# bloxa.net
KiCad netlist of a schematic drawn in EAGLE
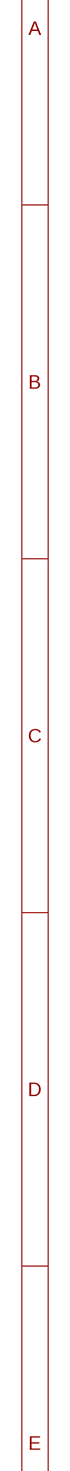
[diagram p0: schematic, sheet 1, part 1 of 2]
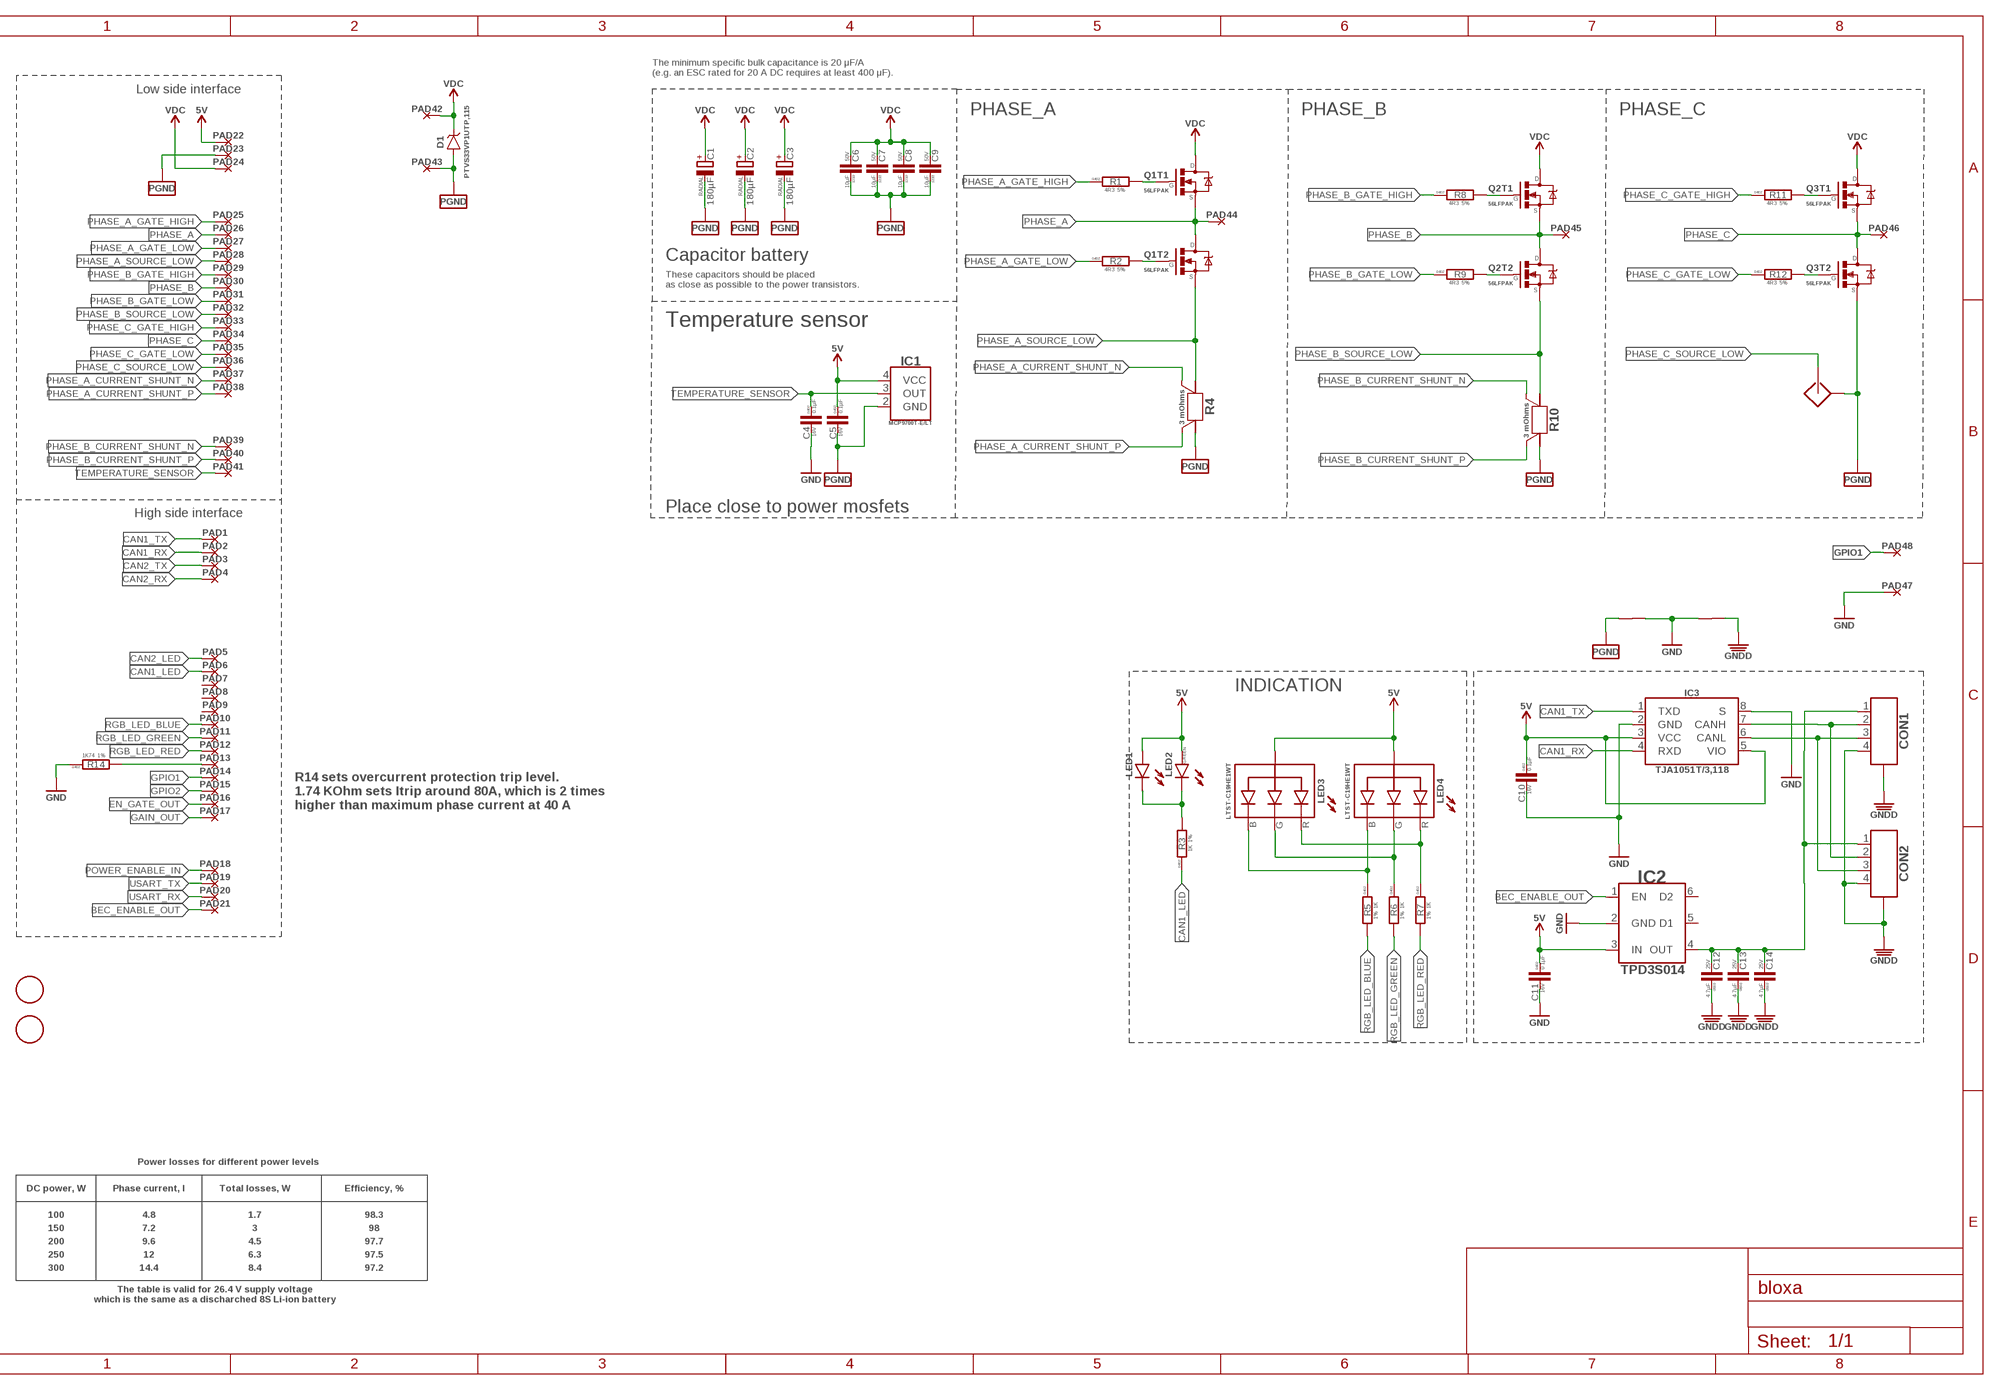
[diagram p1: schematic, sheet 1, part 2 of 2]

(export (version "E")
  (design (tool "Eeschema 10.0.6"))
  (components
    (comp (ref "C1")
      (value "180µF")
      (footprint "eagle-import:RADIAL_SIDE_8X21.5")
      (fields
        (field (name "PACKAGE") "RADIAL")
        (field (name "MANF") "United Chemi-Con")
        (field (name "VOLTAGE") "50V")
      )
      (libsource (lib "eagle-import") (part "CPOL-RADIAL_SIDE-8X21.5"))
    )
    (comp (ref "C2")
      (value "180µF")
      (footprint "eagle-import:RADIAL_SIDE_8X21.5")
      (fields
        (field (name "PACKAGE") "RADIAL")
        (field (name "MANF") "United Chemi-Con")
        (field (name "VOLTAGE") "50V")
      )
      (libsource (lib "eagle-import") (part "CPOL-RADIAL_SIDE-8X21.5"))
    )
    (comp (ref "C3")
      (value "180µF")
      (footprint "eagle-import:RADIAL_SIDE_8X21.5")
      (fields
        (field (name "PACKAGE") "RADIAL")
        (field (name "MANF") "United Chemi-Con")
        (field (name "VOLTAGE") "50V")
      )
      (libsource (lib "eagle-import") (part "CPOL-RADIAL_SIDE-8X21.5"))
    )
    (comp (ref "C4")
      (value "0.1µF")
      (footprint "eagle-import:C0402")
      (fields
        (field (name "MANF") "Murata Electronics North America")
        (field (name "PACKAGE") "0402")
        (field (name "TOLERANCE") "+-10%")
        (field (name "VOLTAGE") "16V")
      )
      (libsource (lib "eagle-import") (part "0.1µF-0402-16V_10%_X7R"))
    )
    (comp (ref "C5")
      (value "0.1µF")
      (footprint "eagle-import:C0402")
      (fields
        (field (name "MANF") "Murata Electronics North America")
        (field (name "PACKAGE") "0402")
        (field (name "TOLERANCE") "+-10%")
        (field (name "VOLTAGE") "16V")
      )
      (libsource (lib "eagle-import") (part "0.1µF-0402-16V_10%_X7R"))
    )
    (comp (ref "C6")
      (value "10µF")
      (footprint "eagle-import:C1210")
      (fields
        (field (name "MANF") "TDK Corporation")
        (field (name "PACKAGE") "1210")
        (field (name "TOLERANCE") "±10%")
        (field (name "VOLTAGE") "50V")
      )
      (libsource (lib "eagle-import") (part "10µF-C1210-50_10%_X7S"))
    )
    (comp (ref "C7")
      (value "10µF")
      (footprint "eagle-import:C1210")
      (fields
        (field (name "MANF") "TDK Corporation")
        (field (name "PACKAGE") "1210")
        (field (name "TOLERANCE") "±10%")
        (field (name "VOLTAGE") "50V")
      )
      (libsource (lib "eagle-import") (part "10µF-C1210-50_10%_X7S"))
    )
    (comp (ref "C8")
      (value "10µF")
      (footprint "eagle-import:C1210")
      (fields
        (field (name "MANF") "TDK Corporation")
        (field (name "PACKAGE") "1210")
        (field (name "TOLERANCE") "±10%")
        (field (name "VOLTAGE") "50V")
      )
      (libsource (lib "eagle-import") (part "10µF-C1210-50_10%_X7S"))
    )
    (comp (ref "C9")
      (value "10µF")
      (footprint "eagle-import:C1210")
      (fields
        (field (name "MANF") "TDK Corporation")
        (field (name "PACKAGE") "1210")
        (field (name "TOLERANCE") "±10%")
        (field (name "VOLTAGE") "50V")
      )
      (libsource (lib "eagle-import") (part "10µF-C1210-50_10%_X7S"))
    )
    (comp (ref "C10")
      (value "0.1µF")
      (footprint "eagle-import:C0402")
      (fields
        (field (name "MANF") "Murata Electronics North America")
        (field (name "PACKAGE") "0402")
        (field (name "TOLERANCE") "+-10%")
        (field (name "VOLTAGE") "16V")
      )
      (libsource (lib "eagle-import") (part "0.1µF-0402-16V_10%_X7R"))
    )
    (comp (ref "C11")
      (value "0.1µF")
      (footprint "eagle-import:C0402")
      (fields
        (field (name "MANF") "Murata Electronics North America")
        (field (name "PACKAGE") "0402")
        (field (name "TOLERANCE") "+-10%")
        (field (name "VOLTAGE") "16V")
      )
      (libsource (lib "eagle-import") (part "0.1µF-0402-16V_10%_X7R"))
    )
    (comp (ref "C12")
      (value "4.7µF")
      (footprint "eagle-import:C0603")
      (fields
        (field (name "MANF") "Murata Electronics North America")
        (field (name "PACKAGE") "0603")
        (field (name "TOLERANCE") "+-10%")
        (field (name "VOLTAGE") "25V")
      )
      (libsource (lib "eagle-import") (part "4.7µF-0603-25V_10%_X6S"))
    )
    (comp (ref "C13")
      (value "4.7µF")
      (footprint "eagle-import:C0603")
      (fields
        (field (name "MANF") "Murata Electronics North America")
        (field (name "PACKAGE") "0603")
        (field (name "TOLERANCE") "+-10%")
        (field (name "VOLTAGE") "25V")
      )
      (libsource (lib "eagle-import") (part "4.7µF-0603-25V_10%_X6S"))
    )
    (comp (ref "C14")
      (value "4.7µF")
      (footprint "eagle-import:C0603")
      (fields
        (field (name "MANF") "Murata Electronics North America")
        (field (name "PACKAGE") "0603")
        (field (name "TOLERANCE") "+-10%")
        (field (name "VOLTAGE") "25V")
      )
      (libsource (lib "eagle-import") (part "4.7µF-0603-25V_10%_X6S"))
    )
    (comp (ref "CON1")
      (value "CON-4P-JST_GH-RA")
      (footprint "eagle-import:JST_GH-4P-RA")
      (fields (field (name "MANF") "JST Sales America Inc"))
      (libsource (lib "eagle-import") (part "CON-4P-RA-JST_GH"))
    )
    (comp (ref "CON2")
      (value "CON-4P-JST_GH-RA")
      (footprint "eagle-import:JST_GH-4P-RA")
      (fields (field (name "MANF") "JST Sales America Inc"))
      (libsource (lib "eagle-import") (part "CON-4P-RA-JST_GH"))
    )
    (comp (ref "D1")
      (value "PTVS33VP1UTP,115-36V-SOD128")
      (footprint "eagle-import:SOD128")
      (fields (field (name "MANF") "Nexperia USA Inc") (field (name "MANF#") "PTVS33VP1UTP,115"))
      (libsource (lib "eagle-import") (part "PTVS33VP1UTP,115-SOD128-36V"))
    )
    (comp (ref "FD1")
      (value "FIDUCIALMOUNT")
      (footprint "eagle-import:FIDUCIA-MOUNT")
      (libsource (lib "eagle-import") (part "FIDUCIALMOUNT"))
    )
    (comp (ref "FD2")
      (value "FIDUCIALMOUNT")
      (footprint "eagle-import:FIDUCIA-MOUNT")
      (libsource (lib "eagle-import") (part "FIDUCIALMOUNT"))
    )
    (comp (ref "IC1")
      (value "MCP9700-SC70-5")
      (footprint "eagle-import:SC70-5")
      (fields (field (name "MANF#") "MCP9700T-E/LT") (field (name "MANF") "Microchip Technology"))
      (libsource (lib "eagle-import") (part "MCP9700-SC70-5"))
    )
    (comp (ref "IC2")
      (value "TPD3S014DBVR-SOT23-6")
      (footprint "eagle-import:SOT26")
      (fields (field (name "MANF") "Texas Instruments"))
      (libsource (lib "eagle-import") (part "TPD3S014DBVR-SOT23-6"))
    )
    (comp (ref "IC3")
      (value "TJA1051(X)/3-SO8")
      (footprint "eagle-import:SOIC8")
      (fields (field (name "MANF#") "TJA1051T/3,118") (field (name "MANF") "NXP USA Inc"))
      (libsource (lib "eagle-import") (part "TJA1051(X)/3-SO8"))
    )
    (comp (ref "J1")
      (value "CONNECTION")
      (footprint "eagle-import:CONNECTION")
      (libsource (lib "eagle-import") (part "CONNECTION"))
    )
    (comp (ref "J2")
      (value "CONNECTION")
      (footprint "eagle-import:CONNECTION")
      (libsource (lib "eagle-import") (part "CONNECTION"))
    )
    (comp (ref "LED1")
      (value "GREEN")
      (footprint "eagle-import:LED0402")
      (libsource (lib "eagle-import") (part "LED-0402"))
    )
    (comp (ref "LED2")
      (value "GREEN")
      (footprint "eagle-import:LED0402")
      (fields
        (field (name "COLOR") "GREEN")
        (field (name "DIGIKEY#") "1830-IN-S42BT5GCT-ND")
        (field (name "MANF") "Inolux")
        (field (name "MANF#") "IN-S42BT5G")
      )
      (libsource (lib "eagle-import") (part "LED-0402"))
    )
    (comp (ref "LED3")
      (value "LTST-C19HE1WT")
      (footprint "eagle-import:0606")
      (fields (field (name "MANF#") "LTST-C19HE1WT") (field (name "MANF") "Lite-On Inc"))
      (libsource (lib "eagle-import") (part "LTST-C19HE1WT"))
    )
    (comp (ref "LED4")
      (value "LTST-C19HE1WT")
      (footprint "eagle-import:0606")
      (fields (field (name "MANF#") "LTST-C19HE1WT") (field (name "MANF") "Lite-On Inc"))
      (libsource (lib "eagle-import") (part "LTST-C19HE1WT"))
    )
    (comp (ref "PAD1")
      (value "PAD-1X1.5")
      (footprint "eagle-import:SMD_1X1,5")
      (libsource (lib "eagle-import") (part "PAD-1X1.5"))
    )
    (comp (ref "PAD2")
      (value "PAD-1X1.5")
      (footprint "eagle-import:SMD_1X1,5")
      (libsource (lib "eagle-import") (part "PAD-1X1.5"))
    )
    (comp (ref "PAD3")
      (value "PAD-1X1.5")
      (footprint "eagle-import:SMD_1X1,5")
      (libsource (lib "eagle-import") (part "PAD-1X1.5"))
    )
    (comp (ref "PAD4")
      (value "PAD-1X1.5")
      (footprint "eagle-import:SMD_1X1,5")
      (libsource (lib "eagle-import") (part "PAD-1X1.5"))
    )
    (comp (ref "PAD5")
      (value "PAD-HOLE-0.6")
      (footprint "eagle-import:HOLE_0.6")
      (libsource (lib "eagle-import") (part "PAD-HOLE-0.6"))
    )
    (comp (ref "PAD6")
      (value "PAD-HOLE-0.6")
      (footprint "eagle-import:HOLE_0.6")
      (libsource (lib "eagle-import") (part "PAD-HOLE-0.6"))
    )
    (comp (ref "PAD7")
      (value "PAD-HOLE-0.6")
      (footprint "eagle-import:HOLE_0.6")
      (libsource (lib "eagle-import") (part "PAD-HOLE-0.6"))
    )
    (comp (ref "PAD8")
      (value "PAD-HOLE-0.6")
      (footprint "eagle-import:HOLE_0.6")
      (libsource (lib "eagle-import") (part "PAD-HOLE-0.6"))
    )
    (comp (ref "PAD9")
      (value "PAD-HOLE-0.6")
      (footprint "eagle-import:HOLE_0.6")
      (libsource (lib "eagle-import") (part "PAD-HOLE-0.6"))
    )
    (comp (ref "PAD10")
      (value "PAD-HOLE-0.6")
      (footprint "eagle-import:HOLE_0.6")
      (libsource (lib "eagle-import") (part "PAD-HOLE-0.6"))
    )
    (comp (ref "PAD11")
      (value "PAD-HOLE-0.6")
      (footprint "eagle-import:HOLE_0.6")
      (libsource (lib "eagle-import") (part "PAD-HOLE-0.6"))
    )
    (comp (ref "PAD12")
      (value "PAD-HOLE-0.6")
      (footprint "eagle-import:HOLE_0.6")
      (libsource (lib "eagle-import") (part "PAD-HOLE-0.6"))
    )
    (comp (ref "PAD13")
      (value "PAD-HOLE-0.6")
      (footprint "eagle-import:HOLE_0.6")
      (libsource (lib "eagle-import") (part "PAD-HOLE-0.6"))
    )
    (comp (ref "PAD14")
      (value "PAD-HOLE-0.6")
      (footprint "eagle-import:HOLE_0.6")
      (libsource (lib "eagle-import") (part "PAD-HOLE-0.6"))
    )
    (comp (ref "PAD15")
      (value "PAD-HOLE-0.6")
      (footprint "eagle-import:HOLE_0.6")
      (libsource (lib "eagle-import") (part "PAD-HOLE-0.6"))
    )
    (comp (ref "PAD16")
      (value "PAD-HOLE-0.6")
      (footprint "eagle-import:HOLE_0.6")
      (libsource (lib "eagle-import") (part "PAD-HOLE-0.6"))
    )
    (comp (ref "PAD17")
      (value "PAD-HOLE-0.6")
      (footprint "eagle-import:HOLE_0.6")
      (libsource (lib "eagle-import") (part "PAD-HOLE-0.6"))
    )
    (comp (ref "PAD18")
      (value "PAD-HOLE-0.6")
      (footprint "eagle-import:HOLE_0.6")
      (libsource (lib "eagle-import") (part "PAD-HOLE-0.6"))
    )
    (comp (ref "PAD19")
      (value "PAD-HOLE-0.6")
      (footprint "eagle-import:HOLE_0.6")
      (libsource (lib "eagle-import") (part "PAD-HOLE-0.6"))
    )
    (comp (ref "PAD20")
      (value "PAD-HOLE-0.6")
      (footprint "eagle-import:HOLE_0.6")
      (libsource (lib "eagle-import") (part "PAD-HOLE-0.6"))
    )
    (comp (ref "PAD21")
      (value "PAD-HOLE-0.6")
      (footprint "eagle-import:HOLE_0.6")
      (libsource (lib "eagle-import") (part "PAD-HOLE-0.6"))
    )
    (comp (ref "PAD22")
      (value "PAD-1X1.5")
      (footprint "eagle-import:SMD_1X1,5")
      (libsource (lib "eagle-import") (part "PAD-1X1.5"))
    )
    (comp (ref "PAD23")
      (value "PAD-1X1.5")
      (footprint "eagle-import:SMD_1X1,5")
      (libsource (lib "eagle-import") (part "PAD-1X1.5"))
    )
    (comp (ref "PAD24")
      (value "PAD-1X1.5")
      (footprint "eagle-import:SMD_1X1,5")
      (libsource (lib "eagle-import") (part "PAD-1X1.5"))
    )
    (comp (ref "PAD25")
      (value "PAD-HOLE-0.6")
      (footprint "eagle-import:HOLE_0.6")
      (libsource (lib "eagle-import") (part "PAD-HOLE-0.6"))
    )
    (comp (ref "PAD26")
      (value "PAD-HOLE-0.6")
      (footprint "eagle-import:HOLE_0.6")
      (libsource (lib "eagle-import") (part "PAD-HOLE-0.6"))
    )
    (comp (ref "PAD27")
      (value "PAD-HOLE-0.6")
      (footprint "eagle-import:HOLE_0.6")
      (libsource (lib "eagle-import") (part "PAD-HOLE-0.6"))
    )
    (comp (ref "PAD28")
      (value "PAD-HOLE-0.6")
      (footprint "eagle-import:HOLE_0.6")
      (libsource (lib "eagle-import") (part "PAD-HOLE-0.6"))
    )
    (comp (ref "PAD29")
      (value "PAD-HOLE-0.6")
      (footprint "eagle-import:HOLE_0.6")
      (libsource (lib "eagle-import") (part "PAD-HOLE-0.6"))
    )
    (comp (ref "PAD30")
      (value "PAD-HOLE-0.6")
      (footprint "eagle-import:HOLE_0.6")
      (libsource (lib "eagle-import") (part "PAD-HOLE-0.6"))
    )
    (comp (ref "PAD31")
      (value "PAD-HOLE-0.6")
      (footprint "eagle-import:HOLE_0.6")
      (libsource (lib "eagle-import") (part "PAD-HOLE-0.6"))
    )
    (comp (ref "PAD32")
      (value "PAD-HOLE-0.6")
      (footprint "eagle-import:HOLE_0.6")
      (libsource (lib "eagle-import") (part "PAD-HOLE-0.6"))
    )
    (comp (ref "PAD33")
      (value "PAD-HOLE-0.6")
      (footprint "eagle-import:HOLE_0.6")
      (libsource (lib "eagle-import") (part "PAD-HOLE-0.6"))
    )
    (comp (ref "PAD34")
      (value "PAD-HOLE-0.6")
      (footprint "eagle-import:HOLE_0.6")
      (libsource (lib "eagle-import") (part "PAD-HOLE-0.6"))
    )
    (comp (ref "PAD35")
      (value "PAD-HOLE-0.6")
      (footprint "eagle-import:HOLE_0.6")
      (libsource (lib "eagle-import") (part "PAD-HOLE-0.6"))
    )
    (comp (ref "PAD36")
      (value "PAD-HOLE-0.6")
      (footprint "eagle-import:HOLE_0.6")
      (libsource (lib "eagle-import") (part "PAD-HOLE-0.6"))
    )
    (comp (ref "PAD37")
      (value "PAD-HOLE-0.6")
      (footprint "eagle-import:HOLE_0.6")
      (libsource (lib "eagle-import") (part "PAD-HOLE-0.6"))
    )
    (comp (ref "PAD38")
      (value "PAD-HOLE-0.6")
      (footprint "eagle-import:HOLE_0.6")
      (libsource (lib "eagle-import") (part "PAD-HOLE-0.6"))
    )
    (comp (ref "PAD39")
      (value "PAD-HOLE-0.6")
      (footprint "eagle-import:HOLE_0.6")
      (libsource (lib "eagle-import") (part "PAD-HOLE-0.6"))
    )
    (comp (ref "PAD40")
      (value "PAD-HOLE-0.6")
      (footprint "eagle-import:HOLE_0.6")
      (libsource (lib "eagle-import") (part "PAD-HOLE-0.6"))
    )
    (comp (ref "PAD41")
      (value "PAD-HOLE-0.6")
      (footprint "eagle-import:HOLE_0.6")
      (libsource (lib "eagle-import") (part "PAD-HOLE-0.6"))
    )
    (comp (ref "PAD42")
      (value "PAD-4X2")
      (footprint "eagle-import:4X2")
      (libsource (lib "eagle-import") (part "PAD-4X2"))
    )
    (comp (ref "PAD43")
      (value "PAD-4X2")
      (footprint "eagle-import:4X2")
      (libsource (lib "eagle-import") (part "PAD-4X2"))
    )
    (comp (ref "PAD44")
      (value "PAD-HOLE_1.5")
      (footprint "eagle-import:HOLE_1.5")
      (libsource (lib "eagle-import") (part "PAD-HOLE_1.5"))
    )
    (comp (ref "PAD45")
      (value "PAD-HOLE_1.5")
      (footprint "eagle-import:HOLE_1.5")
      (libsource (lib "eagle-import") (part "PAD-HOLE_1.5"))
    )
    (comp (ref "PAD46")
      (value "PAD-HOLE_1.5")
      (footprint "eagle-import:HOLE_1.5")
      (libsource (lib "eagle-import") (part "PAD-HOLE_1.5"))
    )
    (comp (ref "PAD47")
      (value "PAD-S-1.5")
      (footprint "eagle-import:1.5X1.5")
      (libsource (lib "eagle-import") (part "PAD-S-1.5"))
    )
    (comp (ref "PAD48")
      (value "PAD-S-1.5")
      (footprint "eagle-import:1.5X1.5")
      (libsource (lib "eagle-import") (part "PAD-S-1.5"))
    )
    (comp (ref "Q1")
      (value "BUK9K6R2-40E,115")
      (footprint "eagle-import:SOT-1205")
      (fields (field (name "PACKAGE") "56LFPAK") (field (name "MANF") "NXP Semiconductors"))
      (libsource (lib "eagle-import") (part "BUK9K6R2-40E,115"))
    )
    (comp (ref "Q2")
      (value "BUK9K6R2-40E,115")
      (footprint "eagle-import:SOT-1205")
      (fields (field (name "PACKAGE") "56LFPAK") (field (name "MANF") "NXP Semiconductors"))
      (libsource (lib "eagle-import") (part "BUK9K6R2-40E,115"))
    )
    (comp (ref "Q3")
      (value "BUK9K6R2-40E,115")
      (footprint "eagle-import:SOT-1205")
      (fields (field (name "PACKAGE") "56LFPAK") (field (name "MANF") "NXP Semiconductors"))
      (libsource (lib "eagle-import") (part "BUK9K6R2-40E,115"))
    )
    (comp (ref "R1")
      (value "4R3")
      (footprint "eagle-import:R0402")
      (fields (field (name "MANF") "Yageo") (field (name "PACKAGE") "0402") (field (name "TOLERANCE") "5%"))
      (libsource (lib "eagle-import") (part "4R3-0402-5%"))
    )
    (comp (ref "R2")
      (value "4R3")
      (footprint "eagle-import:R0402")
      (fields (field (name "MANF") "Yageo") (field (name "PACKAGE") "0402") (field (name "TOLERANCE") "5%"))
      (libsource (lib "eagle-import") (part "4R3-0402-5%"))
    )
    (comp (ref "R3")
      (value "1K")
      (footprint "eagle-import:R0402")
      (fields (field (name "MANF") "Yageo") (field (name "PACKAGE") "0402") (field (name "TOLERANCE") "1%"))
      (libsource (lib "eagle-import") (part "1K-0402-1%"))
    )
    (comp (ref "R4")
      (value "3 mOhms")
      (footprint "eagle-import:R2512-KELVIN")
      (fields
        (field (name "MANF") "Stackpole Electronics Inc")
        (field (name "POWER") "2W")
        (field (name "TOLERANCE") "±1%")
        (field (name "DIGIKEY#") "2019-TLR3APSDTE3L00F50CT-ND")
        (field (name "MANF_1") "KOA Speer Electronics, Inc.")
        (field (name "MANF#") "TLR3APSDTE3L00F50")
        (field (name "POWER_1") "5W")
      )
      (libsource (lib "eagle-import") (part "CURRENT_SHUNT_KELVIN-2512-KELVIN-0.010R"))
    )
    (comp (ref "R5")
      (value "1K")
      (footprint "eagle-import:R0402")
      (fields (field (name "MANF") "Yageo") (field (name "PACKAGE") "0402") (field (name "TOLERANCE") "1%"))
      (libsource (lib "eagle-import") (part "1K-0402-1%"))
    )
    (comp (ref "R6")
      (value "1K")
      (footprint "eagle-import:R0402")
      (fields (field (name "MANF") "Yageo") (field (name "PACKAGE") "0402") (field (name "TOLERANCE") "1%"))
      (libsource (lib "eagle-import") (part "1K-0402-1%"))
    )
    (comp (ref "R7")
      (value "1K")
      (footprint "eagle-import:R0402")
      (fields (field (name "MANF") "Yageo") (field (name "PACKAGE") "0402") (field (name "TOLERANCE") "1%"))
      (libsource (lib "eagle-import") (part "1K-0402-1%"))
    )
    (comp (ref "R8")
      (value "4R3")
      (footprint "eagle-import:R0402")
      (fields (field (name "MANF") "Yageo") (field (name "PACKAGE") "0402") (field (name "TOLERANCE") "5%"))
      (libsource (lib "eagle-import") (part "4R3-0402-5%"))
    )
    (comp (ref "R9")
      (value "4R3")
      (footprint "eagle-import:R0402")
      (fields (field (name "MANF") "Yageo") (field (name "PACKAGE") "0402") (field (name "TOLERANCE") "5%"))
      (libsource (lib "eagle-import") (part "4R3-0402-5%"))
    )
    (comp (ref "R10")
      (value "3 mOhms")
      (footprint "eagle-import:R2512-KELVIN")
      (fields
        (field (name "MANF") "Stackpole Electronics Inc")
        (field (name "POWER") "2W")
        (field (name "TOLERANCE") "±1%")
        (field (name "DIGIKEY#") "2019-TLR3APSDTE3L00F50CT-ND")
        (field (name "MANF_1") "KOA Speer Electronics, Inc.")
        (field (name "MANF#") "TLR3APSDTE3L00F50")
        (field (name "POWER_1") "5W")
      )
      (libsource (lib "eagle-import") (part "CURRENT_SHUNT_KELVIN-2512-KELVIN-0.010R"))
    )
    (comp (ref "R11")
      (value "4R3")
      (footprint "eagle-import:R0402")
      (fields (field (name "MANF") "Yageo") (field (name "PACKAGE") "0402") (field (name "TOLERANCE") "5%"))
      (libsource (lib "eagle-import") (part "4R3-0402-5%"))
    )
    (comp (ref "R12")
      (value "4R3")
      (footprint "eagle-import:R0402")
      (fields (field (name "MANF") "Yageo") (field (name "PACKAGE") "0402") (field (name "TOLERANCE") "5%"))
      (libsource (lib "eagle-import") (part "4R3-0402-5%"))
    )
    (comp (ref "R14")
      (value "1K74")
      (footprint "eagle-import:R0402")
      (fields
        (field (name "PACKAGE") "0402")
        (field (name "TOLERANCE") "1%")
        (field (name "AEC-Q") "AEC-Q200")
        (field (name "DIGIKEY#") "541-1.74KLCT-ND")
        (field (name "MANF") "Vishay Dale")
        (field (name "MANF#") "CRCW04021K74FKED")
      )
      (libsource (lib "eagle-import") (part "R-0402-1%"))
    )
    (comp (ref "S1")
      (value "SENSE")
      (footprint "eagle-import:SENSE-0.6")
      (libsource (lib "eagle-import") (part "SENSE"))
    )
  )
  (nets
    (net (code "1") (name "5V") (class "Default")
      (node (ref "C10") (pin "1") (pinfunction "1_1") (pintype "passive"))
      (node (ref "C11") (pin "1") (pinfunction "1_1") (pintype "passive"))
      (node (ref "C5") (pin "1") (pinfunction "1_1") (pintype "passive"))
      (node (ref "IC1") (pin "4") (pinfunction "VCC_4") (pintype "bidirectional"))
      (node (ref "IC2") (pin "3") (pinfunction "IN_3") (pintype "bidirectional"))
      (node (ref "IC3") (pin "3") (pinfunction "VCC_3") (pintype "bidirectional"))
      (node (ref "IC3") (pin "5") (pinfunction "VIO_5") (pintype "bidirectional"))
      (node (ref "LED1") (pin "A") (pinfunction "A_A") (pintype "bidirectional"))
      (node (ref "LED2") (pin "A") (pinfunction "A_A") (pintype "bidirectional"))
      (node (ref "LED3") (pin "+") (pinfunction "A_+") (pintype "bidirectional"))
      (node (ref "LED4") (pin "+") (pinfunction "A_+") (pintype "bidirectional"))
      (node (ref "PAD22") (pin "P$1") (pinfunction "P$1_P$1") (pintype "bidirectional"))
    )
    (net (code "2") (name "BEC_ENABLE_OUT") (class "Default")
      (node (ref "IC2") (pin "1") (pinfunction "EN_1") (pintype "bidirectional"))
      (node (ref "PAD21") (pin "P$1") (pinfunction "P$1_P$1") (pintype "bidirectional"))
    )
    (net (code "3") (name "CAN1_LED") (class "Default")
      (node (ref "PAD6") (pin "P$1") (pinfunction "P$1_P$1") (pintype "bidirectional"))
      (node (ref "R3") (pin "1") (pinfunction "1_1") (pintype "passive"))
    )
    (net (code "4") (name "CAN1_RX") (class "Default")
      (node (ref "IC3") (pin "4") (pinfunction "RXD_4") (pintype "bidirectional"))
      (node (ref "PAD2") (pin "P$1") (pinfunction "P$1_P$1") (pintype "bidirectional"))
    )
    (net (code "5") (name "CAN1_TX") (class "Default")
      (node (ref "IC3") (pin "1") (pinfunction "TXD_1") (pintype "bidirectional"))
      (node (ref "PAD1") (pin "P$1") (pinfunction "P$1_P$1") (pintype "bidirectional"))
    )
    (net (code "6") (name "CAN2_LED") (class "Default")
      (node (ref "PAD5") (pin "P$1") (pinfunction "P$1_P$1") (pintype "bidirectional"))
    )
    (net (code "7") (name "CAN2_RX") (class "Default")
      (node (ref "PAD4") (pin "P$1") (pinfunction "P$1_P$1") (pintype "bidirectional"))
    )
    (net (code "8") (name "CAN2_TX") (class "Default")
      (node (ref "PAD3") (pin "P$1") (pinfunction "P$1_P$1") (pintype "bidirectional"))
    )
    (net (code "9") (name "EN_GATE_OUT") (class "Default")
      (node (ref "PAD16") (pin "P$1") (pinfunction "P$1_P$1") (pintype "bidirectional"))
    )
    (net (code "10") (name "GAIN_OUT") (class "Default")
      (node (ref "PAD17") (pin "P$1") (pinfunction "P$1_P$1") (pintype "bidirectional"))
    )
    (net (code "11") (name "GND") (class "Default")
      (node (ref "C10") (pin "2") (pinfunction "2_2") (pintype "passive"))
      (node (ref "C11") (pin "2") (pinfunction "2_2") (pintype "passive"))
      (node (ref "C4") (pin "2") (pinfunction "2_2") (pintype "passive"))
      (node (ref "IC2") (pin "2") (pinfunction "GND_2") (pintype "bidirectional"))
      (node (ref "IC3") (pin "2") (pinfunction "GND_2") (pintype "bidirectional"))
      (node (ref "IC3") (pin "8") (pinfunction "S_8") (pintype "bidirectional"))
      (node (ref "J1") (pin "P$1") (pinfunction "P$1_P$1") (pintype "bidirectional"))
      (node (ref "J2") (pin "P$1") (pinfunction "P$1_P$1") (pintype "bidirectional"))
      (node (ref "PAD47") (pin "P$1") (pinfunction "P$1_P$1") (pintype "bidirectional"))
      (node (ref "R14") (pin "1") (pinfunction "1_1") (pintype "passive"))
    )
    (net (code "12") (name "GNDD") (class "Default")
      (node (ref "C12") (pin "P$1") (pinfunction "1_P$1") (pintype "passive"))
      (node (ref "C13") (pin "P$1") (pinfunction "1_P$1") (pintype "passive"))
      (node (ref "C14") (pin "P$1") (pinfunction "1_P$1") (pintype "passive"))
      (node (ref "CON1") (pin "4") (pinfunction "4_4") (pintype "bidirectional"))
      (node (ref "CON1") (pin "M$0") (pinfunction "GND_M$0") (pintype "bidirectional"))
      (node (ref "CON1") (pin "M$1") (pinfunction "GND_M$1") (pintype "bidirectional"))
      (node (ref "CON2") (pin "4") (pinfunction "4_4") (pintype "bidirectional"))
      (node (ref "CON2") (pin "M$0") (pinfunction "GND_M$0") (pintype "bidirectional"))
      (node (ref "CON2") (pin "M$1") (pinfunction "GND_M$1") (pintype "bidirectional"))
      (node (ref "J2") (pin "P$2") (pinfunction "P$2_P$2") (pintype "bidirectional"))
    )
    (net (code "13") (name "GPIO1") (class "Default")
      (node (ref "PAD14") (pin "P$1") (pinfunction "P$1_P$1") (pintype "bidirectional"))
      (node (ref "PAD48") (pin "P$1") (pinfunction "P$1_P$1") (pintype "bidirectional"))
    )
    (net (code "14") (name "GPIO2") (class "Default")
      (node (ref "PAD15") (pin "P$1") (pinfunction "P$1_P$1") (pintype "bidirectional"))
    )
    (net (code "15") (name "Net-(C12-2)") (class "Default")
      (node (ref "C12") (pin "P$2") (pinfunction "2_P$2") (pintype "passive"))
      (node (ref "C13") (pin "P$2") (pinfunction "2_P$2") (pintype "passive"))
      (node (ref "C14") (pin "P$2") (pinfunction "2_P$2") (pintype "passive"))
      (node (ref "CON1") (pin "1") (pinfunction "1_1") (pintype "bidirectional"))
      (node (ref "CON2") (pin "1") (pinfunction "1_1") (pintype "bidirectional"))
      (node (ref "IC2") (pin "4") (pinfunction "OUT_4") (pintype "bidirectional"))
    )
    (net (code "16") (name "Net-(IC3-CANH)") (class "Default")
      (node (ref "CON1") (pin "2") (pinfunction "2_2") (pintype "bidirectional"))
      (node (ref "CON2") (pin "2") (pinfunction "2_2") (pintype "bidirectional"))
      (node (ref "IC3") (pin "7") (pinfunction "CANH_7") (pintype "bidirectional"))
    )
    (net (code "17") (name "Net-(IC3-CANL)") (class "Default")
      (node (ref "CON1") (pin "3") (pinfunction "3_3") (pintype "bidirectional"))
      (node (ref "CON2") (pin "3") (pinfunction "3_3") (pintype "bidirectional"))
      (node (ref "IC3") (pin "6") (pinfunction "CANL_6") (pintype "bidirectional"))
    )
    (net (code "18") (name "Net-(LED1-PadC)") (class "Default")
      (node (ref "LED1") (pin "C") (pinfunction "C_C") (pintype "bidirectional"))
      (node (ref "LED2") (pin "C") (pinfunction "C_C") (pintype "bidirectional"))
      (node (ref "R3") (pin "2") (pinfunction "2_2") (pintype "passive"))
    )
    (net (code "19") (name "Net-(LED3-PadB)") (class "Default")
      (node (ref "LED3") (pin "B") (pinfunction "B_B") (pintype "bidirectional"))
      (node (ref "LED4") (pin "B") (pinfunction "B_B") (pintype "bidirectional"))
      (node (ref "R5") (pin "1") (pinfunction "1_1") (pintype "passive"))
    )
    (net (code "20") (name "Net-(LED3-PadG)") (class "Default")
      (node (ref "LED3") (pin "G") (pinfunction "G_G") (pintype "bidirectional"))
      (node (ref "LED4") (pin "G") (pinfunction "G_G") (pintype "bidirectional"))
      (node (ref "R6") (pin "1") (pinfunction "1_1") (pintype "passive"))
    )
    (net (code "21") (name "Net-(LED3-PadR)") (class "Default")
      (node (ref "LED3") (pin "R") (pinfunction "R_R") (pintype "bidirectional"))
      (node (ref "LED4") (pin "R") (pinfunction "R_R") (pintype "bidirectional"))
      (node (ref "R7") (pin "1") (pinfunction "1_1") (pintype "passive"))
    )
    (net (code "22") (name "Net-(PAD13-PadP$1)") (class "Default")
      (node (ref "PAD13") (pin "P$1") (pinfunction "P$1_P$1") (pintype "bidirectional"))
      (node (ref "R14") (pin "2") (pinfunction "2_2") (pintype "passive"))
    )
    (net (code "23") (name "Net-(Q1A-G)") (class "Default")
      (node (ref "Q1") (pin "2") (pinfunction "G_2") (pintype "passive"))
      (node (ref "R1") (pin "2") (pinfunction "2_2") (pintype "passive"))
    )
    (net (code "24") (name "Net-(Q1B-G)") (class "Default")
      (node (ref "Q1") (pin "4") (pinfunction "G_4") (pintype "passive"))
      (node (ref "R2") (pin "2") (pinfunction "2_2") (pintype "passive"))
    )
    (net (code "25") (name "Net-(Q2A-G)") (class "Default")
      (node (ref "Q2") (pin "2") (pinfunction "G_2") (pintype "passive"))
      (node (ref "R8") (pin "2") (pinfunction "2_2") (pintype "passive"))
    )
    (net (code "26") (name "Net-(Q2B-G)") (class "Default")
      (node (ref "Q2") (pin "4") (pinfunction "G_4") (pintype "passive"))
      (node (ref "R9") (pin "2") (pinfunction "2_2") (pintype "passive"))
    )
    (net (code "27") (name "Net-(Q3A-G)") (class "Default")
      (node (ref "Q3") (pin "2") (pinfunction "G_2") (pintype "passive"))
      (node (ref "R11") (pin "2") (pinfunction "2_2") (pintype "passive"))
    )
    (net (code "28") (name "Net-(Q3B-G)") (class "Default")
      (node (ref "Q3") (pin "4") (pinfunction "G_4") (pintype "passive"))
      (node (ref "R12") (pin "2") (pinfunction "2_2") (pintype "passive"))
    )
    (net (code "29") (name "PGND") (class "Default")
      (node (ref "C1") (pin "-") (pinfunction "-_-") (pintype "passive"))
      (node (ref "C2") (pin "-") (pinfunction "-_-") (pintype "passive"))
      (node (ref "C3") (pin "-") (pinfunction "-_-") (pintype "passive"))
      (node (ref "C5") (pin "2") (pinfunction "2_2") (pintype "passive"))
      (node (ref "C6") (pin "1") (pinfunction "1_1") (pintype "passive"))
      (node (ref "C7") (pin "1") (pinfunction "1_1") (pintype "passive"))
      (node (ref "C8") (pin "1") (pinfunction "1_1") (pintype "passive"))
      (node (ref "C9") (pin "1") (pinfunction "1_1") (pintype "passive"))
      (node (ref "D1") (pin "A") (pinfunction "A_A") (pintype "passive"))
      (node (ref "IC1") (pin "2") (pinfunction "GND_2") (pintype "bidirectional"))
      (node (ref "J1") (pin "P$2") (pinfunction "P$2_P$2") (pintype "bidirectional"))
      (node (ref "PAD23") (pin "P$1") (pinfunction "P$1_P$1") (pintype "bidirectional"))
      (node (ref "PAD43") (pin "P$1") (pinfunction "P$1_P$1") (pintype "bidirectional"))
      (node (ref "Q3") (pin "3") (pinfunction "S_3") (pintype "passive"))
      (node (ref "R10") (pin "2") (pinfunction "2_2") (pintype "bidirectional"))
      (node (ref "R10") (pin "22") (pinfunction "2_22") (pintype "bidirectional"))
      (node (ref "R4") (pin "2") (pinfunction "2_2") (pintype "bidirectional"))
      (node (ref "R4") (pin "22") (pinfunction "2_22") (pintype "bidirectional"))
      (node (ref "S1") (pin "SHELL") (pinfunction "SHELLL_SHELL") (pintype "bidirectional"))
    )
    (net (code "30") (name "PHASE_A") (class "Default")
      (node (ref "PAD26") (pin "P$1") (pinfunction "P$1_P$1") (pintype "bidirectional"))
      (node (ref "PAD44") (pin "P$1") (pinfunction "P$1_P$1") (pintype "bidirectional"))
      (node (ref "Q1") (pin "1") (pinfunction "S_1") (pintype "passive"))
      (node (ref "Q1") (pin "5") (pinfunction "D_5") (pintype "passive"))
      (node (ref "Q1") (pin "6") (pinfunction "D_6") (pintype "passive"))
      (node (ref "Q1") (pin "EP-5-6") (pinfunction "D_EP-5-6") (pintype "passive"))
    )
    (net (code "31") (name "PHASE_A_CURRENT_SHUNT_N") (class "Default")
      (node (ref "PAD37") (pin "P$1") (pinfunction "P$1_P$1") (pintype "bidirectional"))
      (node (ref "R4") (pin "S1") (pinfunction "S1_S1") (pintype "bidirectional"))
    )
    (net (code "32") (name "PHASE_A_CURRENT_SHUNT_P") (class "Default")
      (node (ref "PAD38") (pin "P$1") (pinfunction "P$1_P$1") (pintype "bidirectional"))
      (node (ref "R4") (pin "S2") (pinfunction "S2_S2") (pintype "bidirectional"))
    )
    (net (code "33") (name "PHASE_A_GATE_HIGH") (class "Default")
      (node (ref "PAD25") (pin "P$1") (pinfunction "P$1_P$1") (pintype "bidirectional"))
      (node (ref "R1") (pin "1") (pinfunction "1_1") (pintype "passive"))
    )
    (net (code "34") (name "PHASE_A_GATE_LOW") (class "Default")
      (node (ref "PAD27") (pin "P$1") (pinfunction "P$1_P$1") (pintype "bidirectional"))
      (node (ref "R2") (pin "1") (pinfunction "1_1") (pintype "passive"))
    )
    (net (code "35") (name "PHASE_A_SOURCE_LOW") (class "Default")
      (node (ref "PAD28") (pin "P$1") (pinfunction "P$1_P$1") (pintype "bidirectional"))
      (node (ref "Q1") (pin "3") (pinfunction "S_3") (pintype "passive"))
      (node (ref "R4") (pin "1") (pinfunction "1_1") (pintype "bidirectional"))
      (node (ref "R4") (pin "11") (pinfunction "1_11") (pintype "bidirectional"))
    )
    (net (code "36") (name "PHASE_B") (class "Default")
      (node (ref "PAD30") (pin "P$1") (pinfunction "P$1_P$1") (pintype "bidirectional"))
      (node (ref "PAD45") (pin "P$1") (pinfunction "P$1_P$1") (pintype "bidirectional"))
      (node (ref "Q2") (pin "1") (pinfunction "S_1") (pintype "passive"))
      (node (ref "Q2") (pin "5") (pinfunction "D_5") (pintype "passive"))
      (node (ref "Q2") (pin "6") (pinfunction "D_6") (pintype "passive"))
      (node (ref "Q2") (pin "EP-5-6") (pinfunction "D_EP-5-6") (pintype "passive"))
    )
    (net (code "37") (name "PHASE_B_CURRENT_SHUNT_N") (class "Default")
      (node (ref "PAD39") (pin "P$1") (pinfunction "P$1_P$1") (pintype "bidirectional"))
      (node (ref "R10") (pin "S1") (pinfunction "S1_S1") (pintype "bidirectional"))
    )
    (net (code "38") (name "PHASE_B_CURRENT_SHUNT_P") (class "Default")
      (node (ref "PAD40") (pin "P$1") (pinfunction "P$1_P$1") (pintype "bidirectional"))
      (node (ref "R10") (pin "S2") (pinfunction "S2_S2") (pintype "bidirectional"))
    )
    (net (code "39") (name "PHASE_B_GATE_HIGH") (class "Default")
      (node (ref "PAD29") (pin "P$1") (pinfunction "P$1_P$1") (pintype "bidirectional"))
      (node (ref "R8") (pin "1") (pinfunction "1_1") (pintype "passive"))
    )
    (net (code "40") (name "PHASE_B_GATE_LOW") (class "Default")
      (node (ref "PAD31") (pin "P$1") (pinfunction "P$1_P$1") (pintype "bidirectional"))
      (node (ref "R9") (pin "1") (pinfunction "1_1") (pintype "passive"))
    )
    (net (code "41") (name "PHASE_B_SOURCE_LOW") (class "Default")
      (node (ref "PAD32") (pin "P$1") (pinfunction "P$1_P$1") (pintype "bidirectional"))
      (node (ref "Q2") (pin "3") (pinfunction "S_3") (pintype "passive"))
      (node (ref "R10") (pin "1") (pinfunction "1_1") (pintype "bidirectional"))
      (node (ref "R10") (pin "11") (pinfunction "1_11") (pintype "bidirectional"))
    )
    (net (code "42") (name "PHASE_C") (class "Default")
      (node (ref "PAD34") (pin "P$1") (pinfunction "P$1_P$1") (pintype "bidirectional"))
      (node (ref "PAD46") (pin "P$1") (pinfunction "P$1_P$1") (pintype "bidirectional"))
      (node (ref "Q3") (pin "1") (pinfunction "S_1") (pintype "passive"))
      (node (ref "Q3") (pin "5") (pinfunction "D_5") (pintype "passive"))
      (node (ref "Q3") (pin "6") (pinfunction "D_6") (pintype "passive"))
      (node (ref "Q3") (pin "EP-5-6") (pinfunction "D_EP-5-6") (pintype "passive"))
    )
    (net (code "43") (name "PHASE_C_GATE_HIGH") (class "Default")
      (node (ref "PAD33") (pin "P$1") (pinfunction "P$1_P$1") (pintype "bidirectional"))
      (node (ref "R11") (pin "1") (pinfunction "1_1") (pintype "passive"))
    )
    (net (code "44") (name "PHASE_C_GATE_LOW") (class "Default")
      (node (ref "PAD35") (pin "P$1") (pinfunction "P$1_P$1") (pintype "bidirectional"))
      (node (ref "R12") (pin "1") (pinfunction "1_1") (pintype "passive"))
    )
    (net (code "45") (name "PHASE_C_SOURCE_LOW") (class "Default")
      (node (ref "PAD36") (pin "P$1") (pinfunction "P$1_P$1") (pintype "bidirectional"))
      (node (ref "S1") (pin "IN") (pinfunction "IN_IN") (pintype "bidirectional"))
    )
    (net (code "46") (name "POWER_ENABLE_IN") (class "Default")
      (node (ref "PAD18") (pin "P$1") (pinfunction "P$1_P$1") (pintype "bidirectional"))
    )
    (net (code "47") (name "RGB_LED_BLUE") (class "Default")
      (node (ref "PAD10") (pin "P$1") (pinfunction "P$1_P$1") (pintype "bidirectional"))
      (node (ref "R5") (pin "2") (pinfunction "2_2") (pintype "passive"))
    )
    (net (code "48") (name "RGB_LED_GREEN") (class "Default")
      (node (ref "PAD11") (pin "P$1") (pinfunction "P$1_P$1") (pintype "bidirectional"))
      (node (ref "R6") (pin "2") (pinfunction "2_2") (pintype "passive"))
    )
    (net (code "49") (name "RGB_LED_RED") (class "Default")
      (node (ref "PAD12") (pin "P$1") (pinfunction "P$1_P$1") (pintype "bidirectional"))
      (node (ref "R7") (pin "2") (pinfunction "2_2") (pintype "passive"))
    )
    (net (code "50") (name "TEMPERATURE_SENSOR") (class "Default")
      (node (ref "C4") (pin "1") (pinfunction "1_1") (pintype "passive"))
      (node (ref "IC1") (pin "3") (pinfunction "OUT_3") (pintype "bidirectional"))
      (node (ref "PAD41") (pin "P$1") (pinfunction "P$1_P$1") (pintype "bidirectional"))
    )
    (net (code "51") (name "USART_RX") (class "Default")
      (node (ref "PAD20") (pin "P$1") (pinfunction "P$1_P$1") (pintype "bidirectional"))
    )
    (net (code "52") (name "USART_TX") (class "Default")
      (node (ref "PAD19") (pin "P$1") (pinfunction "P$1_P$1") (pintype "bidirectional"))
    )
    (net (code "53") (name "VDC") (class "Default")
      (node (ref "C1") (pin "+") (pinfunction "+_+") (pintype "passive"))
      (node (ref "C2") (pin "+") (pinfunction "+_+") (pintype "passive"))
      (node (ref "C3") (pin "+") (pinfunction "+_+") (pintype "passive"))
      (node (ref "C6") (pin "2") (pinfunction "2_2") (pintype "passive"))
      (node (ref "C7") (pin "2") (pinfunction "2_2") (pintype "passive"))
      (node (ref "C8") (pin "2") (pinfunction "2_2") (pintype "passive"))
      (node (ref "C9") (pin "2") (pinfunction "2_2") (pintype "passive"))
      (node (ref "D1") (pin "C") (pinfunction "C_C") (pintype "passive"))
      (node (ref "PAD24") (pin "P$1") (pinfunction "P$1_P$1") (pintype "bidirectional"))
      (node (ref "PAD42") (pin "P$1") (pinfunction "P$1_P$1") (pintype "bidirectional"))
      (node (ref "Q1") (pin "7") (pinfunction "D_7") (pintype "passive"))
      (node (ref "Q1") (pin "8") (pinfunction "D_8") (pintype "passive"))
      (node (ref "Q1") (pin "EP-7-8") (pinfunction "D_EP-7-8") (pintype "passive"))
      (node (ref "Q2") (pin "7") (pinfunction "D_7") (pintype "passive"))
      (node (ref "Q2") (pin "8") (pinfunction "D_8") (pintype "passive"))
      (node (ref "Q2") (pin "EP-7-8") (pinfunction "D_EP-7-8") (pintype "passive"))
      (node (ref "Q3") (pin "7") (pinfunction "D_7") (pintype "passive"))
      (node (ref "Q3") (pin "8") (pinfunction "D_8") (pintype "passive"))
      (node (ref "Q3") (pin "EP-7-8") (pinfunction "D_EP-7-8") (pintype "passive"))
    )
    (net (code "54") (name "unconnected-(IC2-D1-Pad5)") (class "Default")
      (node (ref "IC2") (pin "5") (pinfunction "D1_5") (pintype "bidirectional"))
    )
    (net (code "55") (name "unconnected-(IC2-D2-Pad6)") (class "Default")
      (node (ref "IC2") (pin "6") (pinfunction "D2_6") (pintype "bidirectional"))
    )
    (net (code "56") (name "unconnected-(PAD7-PadP$1)") (class "Default")
      (node (ref "PAD7") (pin "P$1") (pinfunction "P$1_P$1") (pintype "bidirectional"))
    )
    (net (code "57") (name "unconnected-(PAD8-PadP$1)") (class "Default")
      (node (ref "PAD8") (pin "P$1") (pinfunction "P$1_P$1") (pintype "bidirectional"))
    )
    (net (code "58") (name "unconnected-(PAD9-PadP$1)") (class "Default")
      (node (ref "PAD9") (pin "P$1") (pinfunction "P$1_P$1") (pintype "bidirectional"))
    )
  )
)
